# outlet_tester.net
KiCad netlist of a schematic drawn in EAGLE
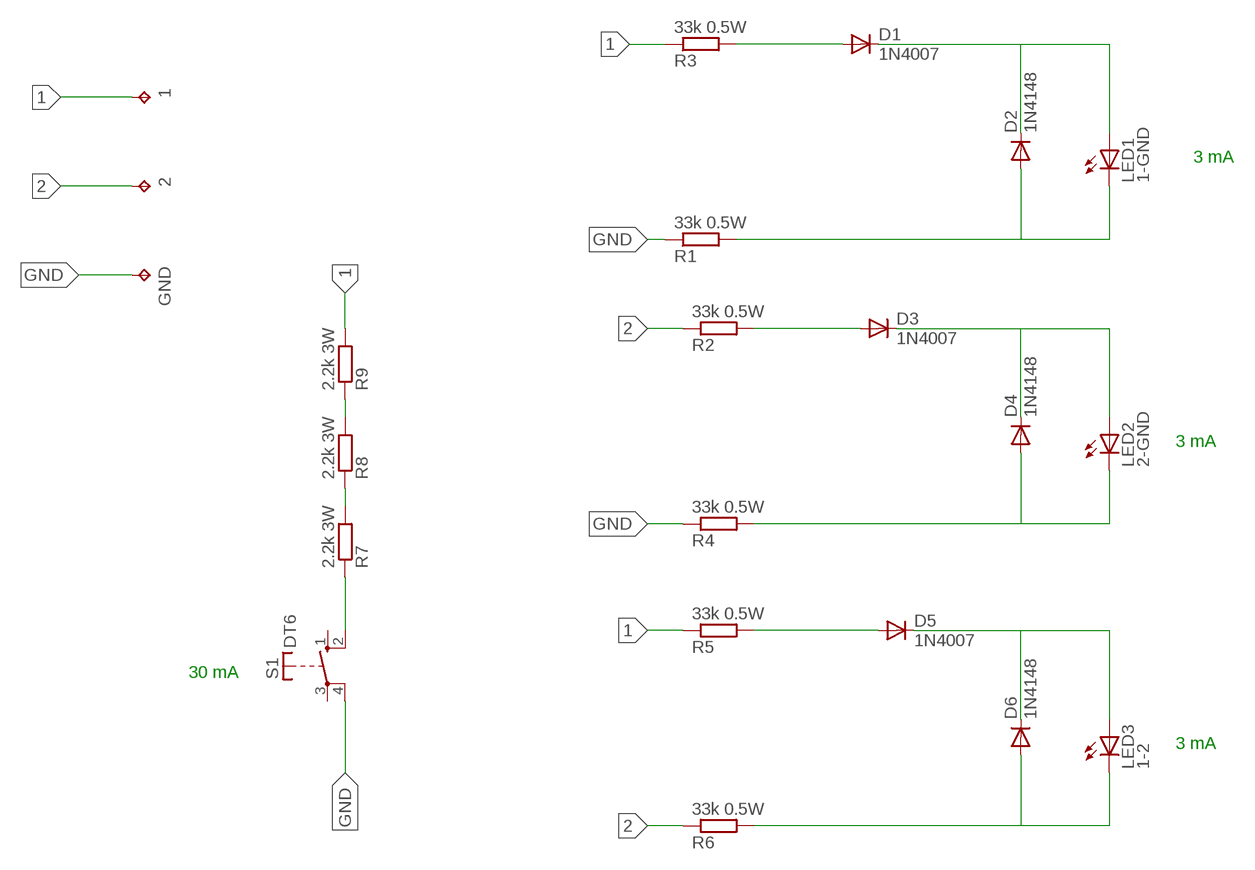
[diagram p0: schematic, sheet 1]

(export (version "E")
  (design (tool "Eeschema 10.0.6"))
  (components
    (comp (ref "1")
      (value "TPPAD1-20")
      (footprint "eagle-import:P1-20")
      (libsource (lib "eagle-import") (part "TPPAD1-20"))
    )
    (comp (ref "2")
      (value "TPPAD1-20")
      (footprint "eagle-import:P1-20")
      (libsource (lib "eagle-import") (part "TPPAD1-20"))
    )
    (comp (ref "D1")
      (value "1N4007")
      (footprint "eagle-import:D-10")
      (libsource (lib "eagle-import") (part "DIODE-D-10"))
    )
    (comp (ref "D2")
      (value "1N4148")
      (footprint "eagle-import:D-10")
      (libsource (lib "eagle-import") (part "DIODE-D-10"))
    )
    (comp (ref "D3")
      (value "1N4007")
      (footprint "eagle-import:D-10")
      (libsource (lib "eagle-import") (part "DIODE-D-10"))
    )
    (comp (ref "D4")
      (value "1N4148")
      (footprint "eagle-import:D-10")
      (libsource (lib "eagle-import") (part "DIODE-D-10"))
    )
    (comp (ref "D5")
      (value "1N4007")
      (footprint "eagle-import:D-10")
      (libsource (lib "eagle-import") (part "DIODE-D-10"))
    )
    (comp (ref "D6")
      (value "1N4148")
      (footprint "eagle-import:D-10")
      (libsource (lib "eagle-import") (part "DIODE-D-10"))
    )
    (comp (ref "GND")
      (value "TPPAD1-20")
      (footprint "eagle-import:P1-20")
      (libsource (lib "eagle-import") (part "TPPAD1-20"))
    )
    (comp (ref "LED1")
      (value "1-GND")
      (footprint "eagle-import:LED5MM")
      (libsource (lib "eagle-import") (part "LED5MM"))
    )
    (comp (ref "LED2")
      (value "2-GND")
      (footprint "eagle-import:LED5MM")
      (libsource (lib "eagle-import") (part "LED5MM"))
    )
    (comp (ref "LED3")
      (value "1-2")
      (footprint "eagle-import:LED5MM")
      (libsource (lib "eagle-import") (part "LED5MM"))
    )
    (comp (ref "R1")
      (value "33k 0.5W")
      (footprint "eagle-import:0207_10")
      (libsource (lib "eagle-import") (part "R-EU_0207/10"))
    )
    (comp (ref "R2")
      (value "33k 0.5W")
      (footprint "eagle-import:0207_10")
      (libsource (lib "eagle-import") (part "R-EU_0207/10"))
    )
    (comp (ref "R3")
      (value "33k 0.5W")
      (footprint "eagle-import:0207_10")
      (libsource (lib "eagle-import") (part "R-EU_0207/10"))
    )
    (comp (ref "R4")
      (value "33k 0.5W")
      (footprint "eagle-import:0207_10")
      (libsource (lib "eagle-import") (part "R-EU_0207/10"))
    )
    (comp (ref "R5")
      (value "33k 0.5W")
      (footprint "eagle-import:0207_10")
      (libsource (lib "eagle-import") (part "R-EU_0207/10"))
    )
    (comp (ref "R6")
      (value "33k 0.5W")
      (footprint "eagle-import:0207_10")
      (libsource (lib "eagle-import") (part "R-EU_0207/10"))
    )
    (comp (ref "R7")
      (value "2.2k 3W")
      (footprint "eagle-import:0207_10")
      (libsource (lib "eagle-import") (part "R-EU_0207/10"))
    )
    (comp (ref "R8")
      (value "2.2k 3W")
      (footprint "eagle-import:0207_10")
      (libsource (lib "eagle-import") (part "R-EU_0207/10"))
    )
    (comp (ref "R9")
      (value "2.2k 3W")
      (footprint "eagle-import:0207_10")
      (libsource (lib "eagle-import") (part "R-EU_0207/10"))
    )
    (comp (ref "S1")
      (value "DT6")
      (footprint "eagle-import:DT6")
      (libsource (lib "eagle-import") (part "DT6"))
    )
  )
  (nets
    (net (code "1") (name "1") (class "Default")
      (node (ref "1") (pin "TP") (pinfunction "TP_TP") (pintype "input"))
      (node (ref "R3") (pin "1") (pinfunction "1_1") (pintype "passive"))
      (node (ref "R5") (pin "1") (pinfunction "1_1") (pintype "passive"))
      (node (ref "R9") (pin "2") (pinfunction "2_2") (pintype "passive"))
    )
    (net (code "2") (name "2") (class "Default")
      (node (ref "2") (pin "TP") (pinfunction "TP_TP") (pintype "input"))
      (node (ref "R2") (pin "1") (pinfunction "1_1") (pintype "passive"))
      (node (ref "R6") (pin "1") (pinfunction "1_1") (pintype "passive"))
    )
    (net (code "3") (name "GND") (class "Default")
      (node (ref "GND") (pin "TP") (pinfunction "TP_TP") (pintype "input"))
      (node (ref "R1") (pin "1") (pinfunction "1_1") (pintype "passive"))
      (node (ref "R4") (pin "1") (pinfunction "1_1") (pintype "passive"))
      (node (ref "S1") (pin "4") (pinfunction "P_4") (pintype "passive"))
    )
    (net (code "4") (name "Net-(D1-PadA)") (class "Default")
      (node (ref "D1") (pin "A") (pinfunction "A_A") (pintype "passive"))
      (node (ref "R3") (pin "2") (pinfunction "2_2") (pintype "passive"))
    )
    (net (code "5") (name "Net-(D1-PadC)") (class "Default")
      (node (ref "D1") (pin "C") (pinfunction "C_C") (pintype "passive"))
      (node (ref "D2") (pin "C") (pinfunction "C_C") (pintype "passive"))
      (node (ref "LED1") (pin "A") (pinfunction "A_A") (pintype "passive"))
    )
    (net (code "6") (name "Net-(D3-PadA)") (class "Default")
      (node (ref "D3") (pin "A") (pinfunction "A_A") (pintype "passive"))
      (node (ref "R2") (pin "2") (pinfunction "2_2") (pintype "passive"))
    )
    (net (code "7") (name "Net-(D3-PadC)") (class "Default")
      (node (ref "D3") (pin "C") (pinfunction "C_C") (pintype "passive"))
      (node (ref "D4") (pin "C") (pinfunction "C_C") (pintype "passive"))
      (node (ref "LED2") (pin "A") (pinfunction "A_A") (pintype "passive"))
    )
    (net (code "8") (name "Net-(D5-PadA)") (class "Default")
      (node (ref "D5") (pin "A") (pinfunction "A_A") (pintype "passive"))
      (node (ref "R5") (pin "2") (pinfunction "2_2") (pintype "passive"))
    )
    (net (code "9") (name "Net-(D5-PadC)") (class "Default")
      (node (ref "D5") (pin "C") (pinfunction "C_C") (pintype "passive"))
      (node (ref "D6") (pin "C") (pinfunction "C_C") (pintype "passive"))
      (node (ref "LED3") (pin "A") (pinfunction "A_A") (pintype "passive"))
    )
    (net (code "10") (name "Net-(LED1-C)") (class "Default")
      (node (ref "D2") (pin "A") (pinfunction "A_A") (pintype "passive"))
      (node (ref "LED1") (pin "K") (pinfunction "C_K") (pintype "passive"))
      (node (ref "R1") (pin "2") (pinfunction "2_2") (pintype "passive"))
    )
    (net (code "11") (name "Net-(LED2-C)") (class "Default")
      (node (ref "D4") (pin "A") (pinfunction "A_A") (pintype "passive"))
      (node (ref "LED2") (pin "K") (pinfunction "C_K") (pintype "passive"))
      (node (ref "R4") (pin "2") (pinfunction "2_2") (pintype "passive"))
    )
    (net (code "12") (name "Net-(LED3-C)") (class "Default")
      (node (ref "D6") (pin "A") (pinfunction "A_A") (pintype "passive"))
      (node (ref "LED3") (pin "K") (pinfunction "C_K") (pintype "passive"))
      (node (ref "R6") (pin "2") (pinfunction "2_2") (pintype "passive"))
    )
    (net (code "13") (name "Net-(R7-Pad1)") (class "Default")
      (node (ref "R7") (pin "1") (pinfunction "1_1") (pintype "passive"))
      (node (ref "S1") (pin "2") (pinfunction "S_2") (pintype "passive"))
    )
    (net (code "14") (name "Net-(R7-Pad2)") (class "Default")
      (node (ref "R7") (pin "2") (pinfunction "2_2") (pintype "passive"))
      (node (ref "R8") (pin "1") (pinfunction "1_1") (pintype "passive"))
    )
    (net (code "15") (name "Net-(R8-Pad2)") (class "Default")
      (node (ref "R8") (pin "2") (pinfunction "2_2") (pintype "passive"))
      (node (ref "R9") (pin "1") (pinfunction "1_1") (pintype "passive"))
    )
    (net (code "16") (name "unconnected-(S1-P-Pad3)") (class "Default")
      (node (ref "S1") (pin "3") (pinfunction "P_3") (pintype "passive"))
    )
    (net (code "17") (name "unconnected-(S1-S-Pad1)") (class "Default")
      (node (ref "S1") (pin "1") (pinfunction "S_1") (pintype "passive"))
    )
  )
)
